# LabPower.net
KiCad netlist of a schematic drawn in EAGLE
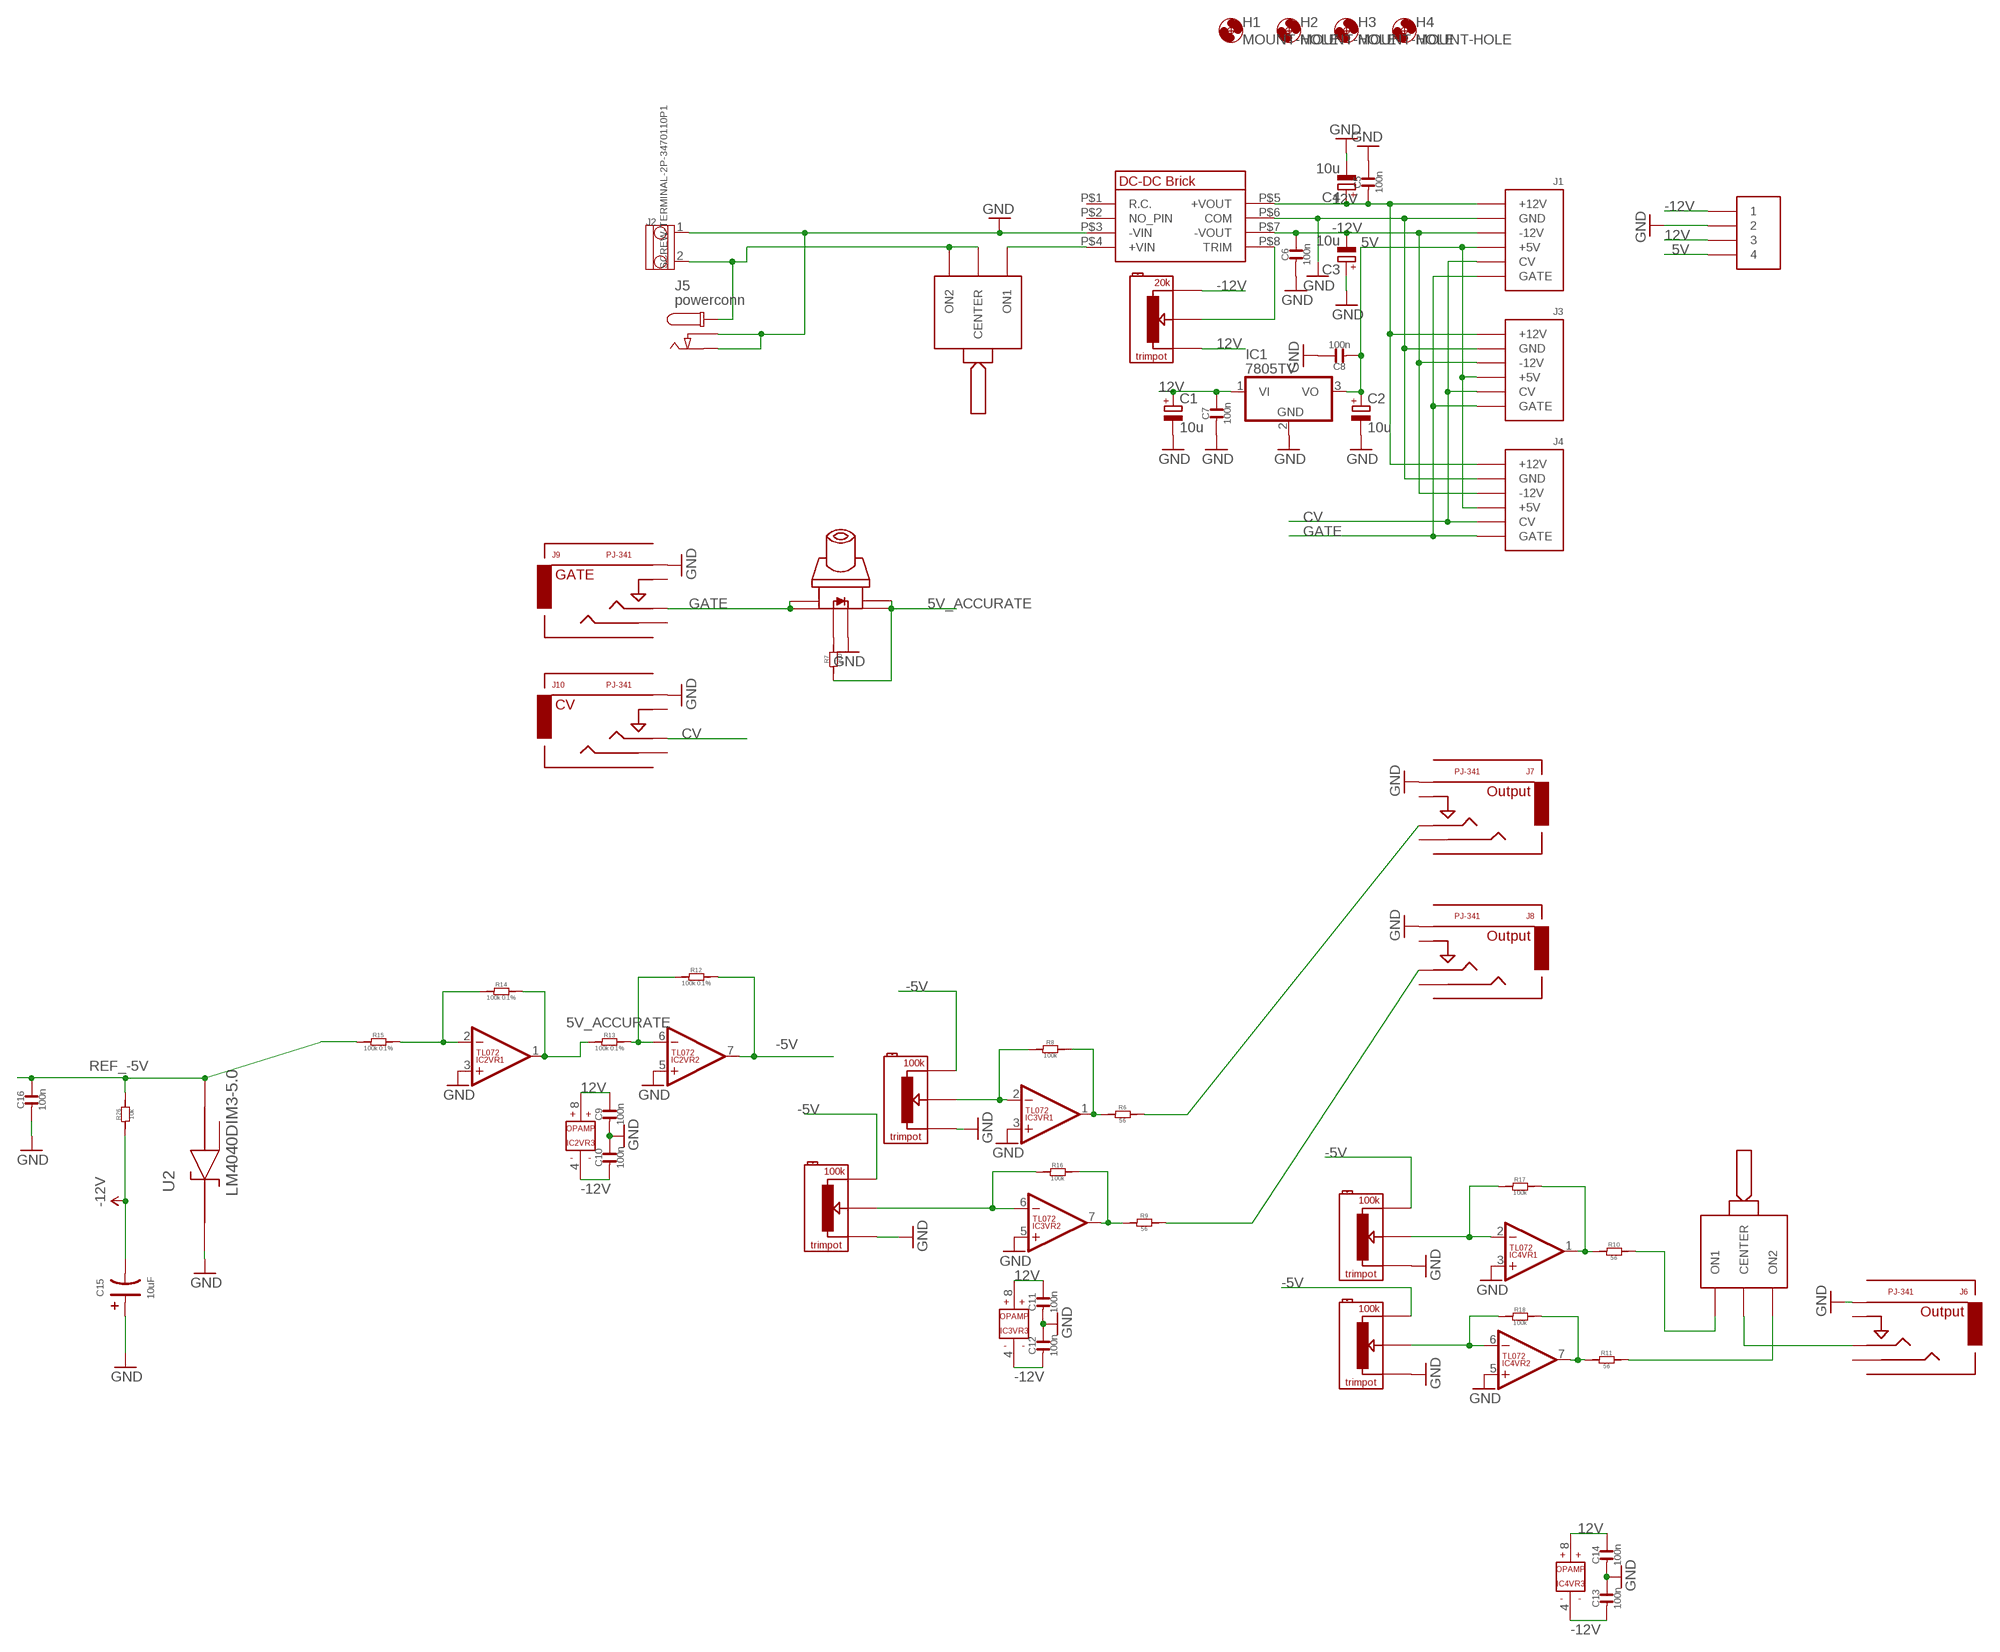
[diagram p0: schematic, sheet 1]

(export (version "E")
  (design (tool "Eeschema 10.0.6"))
  (components
    (comp (ref "C1")
      (value "10u")
      (footprint "eagle-import:CASE_B")
      (libsource (lib "eagle-import") (part "CAPACITOR_POL-CASE_B"))
    )
    (comp (ref "C2")
      (value "10u")
      (footprint "eagle-import:CASE_B")
      (libsource (lib "eagle-import") (part "CAPACITOR_POL-CASE_B"))
    )
    (comp (ref "C3")
      (value "10u")
      (footprint "eagle-import:CASE_B")
      (libsource (lib "eagle-import") (part "CAPACITOR_POL-CASE_B"))
    )
    (comp (ref "C4")
      (value "10u")
      (footprint "eagle-import:CASE_B")
      (libsource (lib "eagle-import") (part "CAPACITOR_POL-CASE_B"))
    )
    (comp (ref "C5")
      (value "100n")
      (footprint "eagle-import:C0603")
      (libsource (lib "eagle-import") (part "C-0603"))
    )
    (comp (ref "C6")
      (value "100n")
      (footprint "eagle-import:C0603")
      (libsource (lib "eagle-import") (part "C-0603"))
    )
    (comp (ref "C7")
      (value "100n")
      (footprint "eagle-import:C0603")
      (libsource (lib "eagle-import") (part "C-0603"))
    )
    (comp (ref "C8")
      (value "100n")
      (footprint "eagle-import:C0603")
      (libsource (lib "eagle-import") (part "C-0603"))
    )
    (comp (ref "C9")
      (value "100n")
      (footprint "eagle-import:C0603")
      (libsource (lib "eagle-import") (part "C-0603"))
    )
    (comp (ref "C10")
      (value "100n")
      (footprint "eagle-import:C0603")
      (libsource (lib "eagle-import") (part "C-0603"))
    )
    (comp (ref "C11")
      (value "100n")
      (footprint "eagle-import:C0603")
      (libsource (lib "eagle-import") (part "C-0603"))
    )
    (comp (ref "C12")
      (value "100n")
      (footprint "eagle-import:C0603")
      (libsource (lib "eagle-import") (part "C-0603"))
    )
    (comp (ref "C13")
      (value "100n")
      (footprint "eagle-import:C0603")
      (libsource (lib "eagle-import") (part "C-0603"))
    )
    (comp (ref "C14")
      (value "100n")
      (footprint "eagle-import:C0603")
      (libsource (lib "eagle-import") (part "C-0603"))
    )
    (comp (ref "C15")
      (value "10uF")
      (footprint "eagle-import:CASE-A_3216")
      (fields (field (name "MF") "AVX") (field (name "MPN") "TAJB106K020RNJ"))
      (libsource (lib "eagle-import") (part "C-POLAR-A"))
    )
    (comp (ref "C16")
      (value "100n")
      (footprint "eagle-import:C0603")
      (fields (field (name "MF") "AVX") (field (name "MPN") "06035C104KAT2A"))
      (libsource (lib "eagle-import") (part "C-0603"))
    )
    (comp (ref "H1")
      (value "MOUNT-HOLE")
      (footprint "eagle-import:3.2-NOMARKINGS-SMALLSAFEZONE")
      (libsource (lib "eagle-import") (part "MOUNT-HOLE"))
    )
    (comp (ref "H2")
      (value "MOUNT-HOLE")
      (footprint "eagle-import:3.2-NOMARKINGS-SMALLSAFEZONE")
      (libsource (lib "eagle-import") (part "MOUNT-HOLE"))
    )
    (comp (ref "H3")
      (value "MOUNT-HOLE")
      (footprint "eagle-import:3.2-NOMARKINGS-SMALLSAFEZONE")
      (libsource (lib "eagle-import") (part "MOUNT-HOLE"))
    )
    (comp (ref "H4")
      (value "MOUNT-HOLE")
      (footprint "eagle-import:3.2-NOMARKINGS-SMALLSAFEZONE")
      (libsource (lib "eagle-import") (part "MOUNT-HOLE"))
    )
    (comp (ref "IC1")
      (value "7805TV")
      (footprint "eagle-import:TO220V")
      (libsource (lib "eagle-import") (part "78TV05"))
    )
    (comp (ref "IC2")
      (value "TL072")
      (footprint "eagle-import:SO08")
      (libsource (lib "eagle-import") (part "TL072"))
    )
    (comp (ref "IC3")
      (value "TL072")
      (footprint "eagle-import:SO08")
      (libsource (lib "eagle-import") (part "TL072"))
    )
    (comp (ref "IC4")
      (value "TL072")
      (footprint "eagle-import:SO08")
      (libsource (lib "eagle-import") (part "TL072"))
    )
    (comp (ref "J1")
      (value "POWERSHROUDED")
      (footprint "eagle-import:POWER_16_SHROUDED")
      (libsource (lib "eagle-import") (part "POWERSHROUDED"))
    )
    (comp (ref "J2")
      (value "SCREW-TERMINAL-2P-3470110P1")
      (footprint "eagle-import:2P-5.0")
      (libsource (lib "eagle-import") (part "SCREW-TERMINAL-2P-3470110P1"))
    )
    (comp (ref "J3")
      (value "POWER_SHROUDED_NOTEXT")
      (footprint "eagle-import:POWER_16_SHROUDED_NOTEXT")
      (libsource (lib "eagle-import") (part "POWER_SHROUDED_NOTEXT"))
    )
    (comp (ref "J4")
      (value "POWER_SHROUDED_NOTEXT")
      (footprint "eagle-import:POWER_16_SHROUDED_NOTEXT")
      (libsource (lib "eagle-import") (part "POWER_SHROUDED_NOTEXT"))
    )
    (comp (ref "J5")
      (value "powerconn")
      (footprint "eagle-import:DC_BARREL_JACK_PTH_2MM_2")
      (libsource (lib "eagle-import") (part "CON_DC_M-DC_PTH2"))
    )
    (comp (ref "J6")
      (value "PJ-341")
      (footprint "eagle-import:3.5MM-JACK-SWITCH-13MM-OUTPUT")
      (libsource (lib "eagle-import") (part "AUDIO-JACKOUTPUT"))
    )
    (comp (ref "J7")
      (value "PJ-341")
      (footprint "eagle-import:3.5MM-JACK-SWITCH-13MM-OUTPUT")
      (libsource (lib "eagle-import") (part "AUDIO-JACKOUTPUT"))
    )
    (comp (ref "J8")
      (value "PJ-341")
      (footprint "eagle-import:3.5MM-JACK-SWITCH-13MM-OUTPUT")
      (libsource (lib "eagle-import") (part "AUDIO-JACKOUTPUT"))
    )
    (comp (ref "J9")
      (value "PJ-341")
      (footprint "eagle-import:3.5MM-JACK-SWITCH-13MM-INPUT")
      (fields (field (name "DESC") "GATE"))
      (libsource (lib "eagle-import") (part "AUDIO-JACKINPUT"))
    )
    (comp (ref "J10")
      (value "PJ-341")
      (footprint "eagle-import:3.5MM-JACK-SWITCH-13MM-INPUT")
      (fields (field (name "DESC") "CV"))
      (libsource (lib "eagle-import") (part "AUDIO-JACKINPUT"))
    )
    (comp (ref "R1")
      (value "20k")
      (footprint "eagle-import:TRIMPOT")
      (libsource (lib "eagle-import") (part "TRIMPOT"))
    )
    (comp (ref "R2")
      (value "100k")
      (footprint "eagle-import:TRIMPOT")
      (libsource (lib "eagle-import") (part "TRIMPOT"))
    )
    (comp (ref "R3")
      (value "100k")
      (footprint "eagle-import:TRIMPOT")
      (libsource (lib "eagle-import") (part "TRIMPOT"))
    )
    (comp (ref "R4")
      (value "100k")
      (footprint "eagle-import:TRIMPOT")
      (libsource (lib "eagle-import") (part "TRIMPOT"))
    )
    (comp (ref "R5")
      (value "100k")
      (footprint "eagle-import:TRIMPOT")
      (libsource (lib "eagle-import") (part "TRIMPOT"))
    )
    (comp (ref "R6")
      (value "56")
      (footprint "eagle-import:R0603")
      (libsource (lib "eagle-import") (part "R-0603"))
    )
    (comp (ref "R7")
      (value "200")
      (footprint "eagle-import:R0603")
      (libsource (lib "eagle-import") (part "R-0603"))
    )
    (comp (ref "R8")
      (value "100k")
      (footprint "eagle-import:R0603")
      (libsource (lib "eagle-import") (part "R-0603"))
    )
    (comp (ref "R9")
      (value "56")
      (footprint "eagle-import:R0603")
      (libsource (lib "eagle-import") (part "R-0603"))
    )
    (comp (ref "R10")
      (value "56")
      (footprint "eagle-import:R0603")
      (libsource (lib "eagle-import") (part "R-0603"))
    )
    (comp (ref "R11")
      (value "56")
      (footprint "eagle-import:R0603")
      (libsource (lib "eagle-import") (part "R-0603"))
    )
    (comp (ref "R12")
      (value "100k 0.1%")
      (footprint "eagle-import:R0603")
      (libsource (lib "eagle-import") (part "R-0603"))
    )
    (comp (ref "R13")
      (value "100k 0.1%")
      (footprint "eagle-import:R0603")
      (libsource (lib "eagle-import") (part "R-0603"))
    )
    (comp (ref "R14")
      (value "100k 0.1%")
      (footprint "eagle-import:R0603")
      (libsource (lib "eagle-import") (part "R-0603"))
    )
    (comp (ref "R15")
      (value "100k 0.1%")
      (footprint "eagle-import:R0603")
      (libsource (lib "eagle-import") (part "R-0603"))
    )
    (comp (ref "R16")
      (value "100k")
      (footprint "eagle-import:R0603")
      (libsource (lib "eagle-import") (part "R-0603"))
    )
    (comp (ref "R17")
      (value "100k")
      (footprint "eagle-import:R0603")
      (libsource (lib "eagle-import") (part "R-0603"))
    )
    (comp (ref "R18")
      (value "100k")
      (footprint "eagle-import:R0603")
      (libsource (lib "eagle-import") (part "R-0603"))
    )
    (comp (ref "R26")
      (value "10k")
      (footprint "eagle-import:R0603")
      (libsource (lib "eagle-import") (part "R-0603"))
    )
    (comp (ref "S1")
      (value "ONOFFON")
      (footprint "eagle-import:MULTICOMP1MS-ONOFFON")
      (libsource (lib "eagle-import") (part "ONOFFON"))
    )
    (comp (ref "S2")
      (value "ONOFFON")
      (footprint "eagle-import:MULTICOMP1MS-ONOFFON")
      (libsource (lib "eagle-import") (part "ONOFFON"))
    )
    (comp (ref "S3")
      (value "SWITCH_W_LED_PB6149L-X-102YELLOW")
      (footprint "eagle-import:PB6149L")
      (libsource (lib "eagle-import") (part "SWITCH_W_LED_PB6149L-X-102YELLOW"))
    )
    (comp (ref "U$1")
      (value "DKA30")
      (footprint "eagle-import:MEANWELL_DKA30")
      (libsource (lib "eagle-import") (part "DKA30"))
    )
    (comp (ref "U$2")
      (value "4PIN5MM")
      (footprint "eagle-import:4PIN5MM")
      (libsource (lib "eagle-import") (part "4PIN5MM"))
    )
    (comp (ref "U2")
      (value "LM4040DIM3-5.0")
      (footprint "eagle-import:SOT95P237X112-3N")
      (fields (field (name "MF") "TEXAS INSTRUMENTS") (field (name "OC_FARNELL") "9778330"))
      (libsource (lib "eagle-import") (part "LM4040DIM3-5.0"))
    )
  )
  (nets
    (net (code "1") (name "-12V") (class "Default")
      (node (ref "C10") (pin "1") (pinfunction "1_1") (pintype "bidirectional"))
      (node (ref "C12") (pin "1") (pinfunction "1_1") (pintype "bidirectional"))
      (node (ref "C13") (pin "1") (pinfunction "1_1") (pintype "bidirectional"))
      (node (ref "C15") (pin "-") (pinfunction "2_-") (pintype "bidirectional"))
      (node (ref "C3") (pin "-") (pinfunction "-_-") (pintype "passive"))
      (node (ref "C6") (pin "2") (pinfunction "2_2") (pintype "bidirectional"))
      (node (ref "IC2") (pin "4") (pinfunction "V-_4") (pintype "power_in"))
      (node (ref "IC3") (pin "4") (pinfunction "V-_4") (pintype "power_in"))
      (node (ref "IC4") (pin "4") (pinfunction "V-_4") (pintype "power_in"))
      (node (ref "J1") (pin "1") (pinfunction "-12V_1") (pintype "bidirectional"))
      (node (ref "J1") (pin "2") (pinfunction "-12V_2") (pintype "bidirectional"))
      (node (ref "J3") (pin "1") (pinfunction "-12V_1") (pintype "bidirectional"))
      (node (ref "J3") (pin "2") (pinfunction "-12V_2") (pintype "bidirectional"))
      (node (ref "J4") (pin "1") (pinfunction "-12V_1") (pintype "bidirectional"))
      (node (ref "J4") (pin "2") (pinfunction "-12V_2") (pintype "bidirectional"))
      (node (ref "R1") (pin "P$3") (pinfunction "P$3_P$3") (pintype "bidirectional"))
      (node (ref "R26") (pin "1") (pinfunction "1_1") (pintype "bidirectional"))
      (node (ref "U$1") (pin "P$7") (pinfunction "-VOUT_P$7") (pintype "bidirectional"))
      (node (ref "U$2") (pin "1") (pinfunction "1_1") (pintype "bidirectional"))
    )
    (net (code "2") (name "/-5V") (class "Default")
      (node (ref "IC2") (pin "7") (pinfunction "OUT_7") (pintype "output"))
      (node (ref "R12") (pin "2") (pinfunction "2_2") (pintype "bidirectional"))
      (node (ref "R2") (pin "P$3") (pinfunction "P$3_P$3") (pintype "bidirectional"))
      (node (ref "R3") (pin "P$3") (pinfunction "P$3_P$3") (pintype "bidirectional"))
      (node (ref "R4") (pin "P$3") (pinfunction "P$3_P$3") (pintype "bidirectional"))
      (node (ref "R5") (pin "P$3") (pinfunction "P$3_P$3") (pintype "bidirectional"))
    )
    (net (code "3") (name "/5V") (class "Default")
      (node (ref "C2") (pin "+") (pinfunction "+_+") (pintype "passive"))
      (node (ref "C8") (pin "1") (pinfunction "1_1") (pintype "bidirectional"))
      (node (ref "IC1") (pin "3") (pinfunction "VO_3") (pintype "passive"))
      (node (ref "J1") (pin "11") (pinfunction "+5V_11") (pintype "bidirectional"))
      (node (ref "J1") (pin "12") (pinfunction "+5V_12") (pintype "bidirectional"))
      (node (ref "J3") (pin "11") (pinfunction "+5V_11") (pintype "bidirectional"))
      (node (ref "J3") (pin "12") (pinfunction "+5V_12") (pintype "bidirectional"))
      (node (ref "J4") (pin "11") (pinfunction "+5V_11") (pintype "bidirectional"))
      (node (ref "J4") (pin "12") (pinfunction "+5V_12") (pintype "bidirectional"))
      (node (ref "U$2") (pin "4") (pinfunction "4_4") (pintype "bidirectional"))
    )
    (net (code "4") (name "/5V_ACCURATE") (class "Default")
      (node (ref "IC2") (pin "1") (pinfunction "OUT_1") (pintype "output"))
      (node (ref "R13") (pin "1") (pinfunction "1_1") (pintype "bidirectional"))
      (node (ref "R14") (pin "2") (pinfunction "2_2") (pintype "bidirectional"))
      (node (ref "R7") (pin "1") (pinfunction "1_1") (pintype "bidirectional"))
      (node (ref "S3") (pin "3") (pinfunction "3_3") (pintype "bidirectional"))
      (node (ref "S3") (pin "4") (pinfunction "4_4") (pintype "bidirectional"))
    )
    (net (code "5") (name "/12V") (class "Default")
      (node (ref "C1") (pin "+") (pinfunction "+_+") (pintype "passive"))
      (node (ref "C11") (pin "2") (pinfunction "2_2") (pintype "bidirectional"))
      (node (ref "C14") (pin "2") (pinfunction "2_2") (pintype "bidirectional"))
      (node (ref "C4") (pin "+") (pinfunction "+_+") (pintype "passive"))
      (node (ref "C5") (pin "1") (pinfunction "1_1") (pintype "bidirectional"))
      (node (ref "C7") (pin "2") (pinfunction "2_2") (pintype "bidirectional"))
      (node (ref "C9") (pin "2") (pinfunction "2_2") (pintype "bidirectional"))
      (node (ref "IC1") (pin "1") (pinfunction "VI_1") (pintype "input"))
      (node (ref "IC2") (pin "8") (pinfunction "V+_8") (pintype "power_in"))
      (node (ref "IC3") (pin "8") (pinfunction "V+_8") (pintype "power_in"))
      (node (ref "IC4") (pin "8") (pinfunction "V+_8") (pintype "power_in"))
      (node (ref "J1") (pin "10") (pinfunction "+12V_10") (pintype "bidirectional"))
      (node (ref "J1") (pin "9") (pinfunction "+12V_9") (pintype "bidirectional"))
      (node (ref "J3") (pin "10") (pinfunction "+12V_10") (pintype "bidirectional"))
      (node (ref "J3") (pin "9") (pinfunction "+12V_9") (pintype "bidirectional"))
      (node (ref "J4") (pin "10") (pinfunction "+12V_10") (pintype "bidirectional"))
      (node (ref "J4") (pin "9") (pinfunction "+12V_9") (pintype "bidirectional"))
      (node (ref "R1") (pin "P$1") (pinfunction "P$1_P$1") (pintype "bidirectional"))
      (node (ref "U$1") (pin "P$5") (pinfunction "+VOUT_P$5") (pintype "bidirectional"))
      (node (ref "U$2") (pin "3") (pinfunction "3_3") (pintype "bidirectional"))
    )
    (net (code "6") (name "/CV") (class "Default")
      (node (ref "J1") (pin "13") (pinfunction "CV_13") (pintype "bidirectional"))
      (node (ref "J1") (pin "14") (pinfunction "CV_14") (pintype "bidirectional"))
      (node (ref "J10") (pin "TIP@3") (pinfunction "TIP_TIP@3") (pintype "bidirectional"))
      (node (ref "J3") (pin "13") (pinfunction "CV_13") (pintype "bidirectional"))
      (node (ref "J3") (pin "14") (pinfunction "CV_14") (pintype "bidirectional"))
      (node (ref "J4") (pin "13") (pinfunction "CV_13") (pintype "bidirectional"))
      (node (ref "J4") (pin "14") (pinfunction "CV_14") (pintype "bidirectional"))
    )
    (net (code "7") (name "/GATE") (class "Default")
      (node (ref "J1") (pin "15") (pinfunction "GATE_15") (pintype "bidirectional"))
      (node (ref "J1") (pin "16") (pinfunction "GATE_16") (pintype "bidirectional"))
      (node (ref "J3") (pin "15") (pinfunction "GATE_15") (pintype "bidirectional"))
      (node (ref "J3") (pin "16") (pinfunction "GATE_16") (pintype "bidirectional"))
      (node (ref "J4") (pin "15") (pinfunction "GATE_15") (pintype "bidirectional"))
      (node (ref "J4") (pin "16") (pinfunction "GATE_16") (pintype "bidirectional"))
      (node (ref "J9") (pin "TIP@3") (pinfunction "TIP_TIP@3") (pintype "bidirectional"))
      (node (ref "S3") (pin "1") (pinfunction "1_1") (pintype "bidirectional"))
      (node (ref "S3") (pin "2") (pinfunction "2_2") (pintype "bidirectional"))
    )
    (net (code "8") (name "/REF_-5V") (class "Default")
      (node (ref "C16") (pin "2") (pinfunction "2_2") (pintype "bidirectional"))
      (node (ref "R15") (pin "1") (pinfunction "1_1") (pintype "bidirectional"))
      (node (ref "R26") (pin "2") (pinfunction "2_2") (pintype "bidirectional"))
      (node (ref "U2") (pin "2") (pinfunction "ANODE_2") (pintype "passive"))
    )
    (net (code "9") (name "GND") (class "Default")
      (node (ref "C1") (pin "-") (pinfunction "-_-") (pintype "passive"))
      (node (ref "C10") (pin "2") (pinfunction "2_2") (pintype "bidirectional"))
      (node (ref "C11") (pin "1") (pinfunction "1_1") (pintype "bidirectional"))
      (node (ref "C12") (pin "2") (pinfunction "2_2") (pintype "bidirectional"))
      (node (ref "C13") (pin "2") (pinfunction "2_2") (pintype "bidirectional"))
      (node (ref "C14") (pin "1") (pinfunction "1_1") (pintype "bidirectional"))
      (node (ref "C15") (pin "+") (pinfunction "1_+") (pintype "bidirectional"))
      (node (ref "C16") (pin "1") (pinfunction "1_1") (pintype "bidirectional"))
      (node (ref "C2") (pin "-") (pinfunction "-_-") (pintype "passive"))
      (node (ref "C3") (pin "+") (pinfunction "+_+") (pintype "passive"))
      (node (ref "C4") (pin "-") (pinfunction "-_-") (pintype "passive"))
      (node (ref "C5") (pin "2") (pinfunction "2_2") (pintype "bidirectional"))
      (node (ref "C6") (pin "1") (pinfunction "1_1") (pintype "bidirectional"))
      (node (ref "C7") (pin "1") (pinfunction "1_1") (pintype "bidirectional"))
      (node (ref "C8") (pin "2") (pinfunction "2_2") (pintype "bidirectional"))
      (node (ref "C9") (pin "1") (pinfunction "1_1") (pintype "bidirectional"))
      (node (ref "IC1") (pin "2") (pinfunction "GND_2") (pintype "passive"))
      (node (ref "IC2") (pin "3") (pinfunction "+IN_3") (pintype "input"))
      (node (ref "IC2") (pin "5") (pinfunction "+IN_5") (pintype "input"))
      (node (ref "IC3") (pin "3") (pinfunction "+IN_3") (pintype "input"))
      (node (ref "IC3") (pin "5") (pinfunction "+IN_5") (pintype "input"))
      (node (ref "IC4") (pin "3") (pinfunction "+IN_3") (pintype "input"))
      (node (ref "IC4") (pin "5") (pinfunction "+IN_5") (pintype "input"))
      (node (ref "J1") (pin "3") (pinfunction "GND_3") (pintype "bidirectional"))
      (node (ref "J1") (pin "4") (pinfunction "GND_4") (pintype "bidirectional"))
      (node (ref "J1") (pin "5") (pinfunction "GND_5") (pintype "bidirectional"))
      (node (ref "J1") (pin "6") (pinfunction "GND_6") (pintype "bidirectional"))
      (node (ref "J1") (pin "7") (pinfunction "GND_7") (pintype "bidirectional"))
      (node (ref "J1") (pin "8") (pinfunction "GND_8") (pintype "bidirectional"))
      (node (ref "J10") (pin "RING@3") (pinfunction "RING_RING@3") (pintype "bidirectional"))
      (node (ref "J2") (pin "1") (pinfunction "1_1") (pintype "bidirectional"))
      (node (ref "J3") (pin "3") (pinfunction "GND_3") (pintype "bidirectional"))
      (node (ref "J3") (pin "4") (pinfunction "GND_4") (pintype "bidirectional"))
      (node (ref "J3") (pin "5") (pinfunction "GND_5") (pintype "bidirectional"))
      (node (ref "J3") (pin "6") (pinfunction "GND_6") (pintype "bidirectional"))
      (node (ref "J3") (pin "7") (pinfunction "GND_7") (pintype "bidirectional"))
      (node (ref "J3") (pin "8") (pinfunction "GND_8") (pintype "bidirectional"))
      (node (ref "J4") (pin "3") (pinfunction "GND_3") (pintype "bidirectional"))
      (node (ref "J4") (pin "4") (pinfunction "GND_4") (pintype "bidirectional"))
      (node (ref "J4") (pin "5") (pinfunction "GND_5") (pintype "bidirectional"))
      (node (ref "J4") (pin "6") (pinfunction "GND_6") (pintype "bidirectional"))
      (node (ref "J4") (pin "7") (pinfunction "GND_7") (pintype "bidirectional"))
      (node (ref "J4") (pin "8") (pinfunction "GND_8") (pintype "bidirectional"))
      (node (ref "J5") (pin "P2") (pinfunction "P3_P2") (pintype "passive"))
      (node (ref "J5") (pin "P3") (pinfunction "P2_P3") (pintype "passive"))
      (node (ref "J6") (pin "RING@3") (pinfunction "RING_RING@3") (pintype "bidirectional"))
      (node (ref "J7") (pin "RING@3") (pinfunction "RING_RING@3") (pintype "bidirectional"))
      (node (ref "J8") (pin "RING@3") (pinfunction "RING_RING@3") (pintype "bidirectional"))
      (node (ref "J9") (pin "RING@3") (pinfunction "RING_RING@3") (pintype "bidirectional"))
      (node (ref "R2") (pin "P$1") (pinfunction "P$1_P$1") (pintype "bidirectional"))
      (node (ref "R3") (pin "P$1") (pinfunction "P$1_P$1") (pintype "bidirectional"))
      (node (ref "R4") (pin "P$1") (pinfunction "P$1_P$1") (pintype "bidirectional"))
      (node (ref "R5") (pin "P$1") (pinfunction "P$1_P$1") (pintype "bidirectional"))
      (node (ref "S3") (pin "LEDNEG") (pinfunction "NEG_LEDNEG") (pintype "bidirectional"))
      (node (ref "U$1") (pin "P$3") (pinfunction "-VIN_P$3") (pintype "bidirectional"))
      (node (ref "U$1") (pin "P$6") (pinfunction "COM_P$6") (pintype "bidirectional"))
      (node (ref "U$2") (pin "2") (pinfunction "2_2") (pintype "bidirectional"))
      (node (ref "U2") (pin "1") (pinfunction "CATHODE_1") (pintype "passive"))
    )
    (net (code "10") (name "Net-(IC2A--IN)") (class "Default")
      (node (ref "IC2") (pin "2") (pinfunction "-IN_2") (pintype "input"))
      (node (ref "R14") (pin "1") (pinfunction "1_1") (pintype "bidirectional"))
      (node (ref "R15") (pin "2") (pinfunction "2_2") (pintype "bidirectional"))
    )
    (net (code "11") (name "Net-(IC2B--IN)") (class "Default")
      (node (ref "IC2") (pin "6") (pinfunction "-IN_6") (pintype "input"))
      (node (ref "R12") (pin "1") (pinfunction "1_1") (pintype "bidirectional"))
      (node (ref "R13") (pin "2") (pinfunction "2_2") (pintype "bidirectional"))
    )
    (net (code "12") (name "Net-(IC3A--IN)") (class "Default")
      (node (ref "IC3") (pin "2") (pinfunction "-IN_2") (pintype "input"))
      (node (ref "R3") (pin "P$2") (pinfunction "P$2_P$2") (pintype "bidirectional"))
      (node (ref "R8") (pin "1") (pinfunction "1_1") (pintype "bidirectional"))
    )
    (net (code "13") (name "Net-(IC3A-OUT)") (class "Default")
      (node (ref "IC3") (pin "1") (pinfunction "OUT_1") (pintype "output"))
      (node (ref "R6") (pin "1") (pinfunction "1_1") (pintype "bidirectional"))
      (node (ref "R8") (pin "2") (pinfunction "2_2") (pintype "bidirectional"))
    )
    (net (code "14") (name "Net-(IC3B--IN)") (class "Default")
      (node (ref "IC3") (pin "6") (pinfunction "-IN_6") (pintype "input"))
      (node (ref "R16") (pin "1") (pinfunction "1_1") (pintype "bidirectional"))
      (node (ref "R4") (pin "P$2") (pinfunction "P$2_P$2") (pintype "bidirectional"))
    )
    (net (code "15") (name "Net-(IC3B-OUT)") (class "Default")
      (node (ref "IC3") (pin "7") (pinfunction "OUT_7") (pintype "output"))
      (node (ref "R16") (pin "2") (pinfunction "2_2") (pintype "bidirectional"))
      (node (ref "R9") (pin "1") (pinfunction "1_1") (pintype "bidirectional"))
    )
    (net (code "16") (name "Net-(IC4A--IN)") (class "Default")
      (node (ref "IC4") (pin "2") (pinfunction "-IN_2") (pintype "input"))
      (node (ref "R17") (pin "1") (pinfunction "1_1") (pintype "bidirectional"))
      (node (ref "R5") (pin "P$2") (pinfunction "P$2_P$2") (pintype "bidirectional"))
    )
    (net (code "17") (name "Net-(IC4A-OUT)") (class "Default")
      (node (ref "IC4") (pin "1") (pinfunction "OUT_1") (pintype "output"))
      (node (ref "R10") (pin "1") (pinfunction "1_1") (pintype "bidirectional"))
      (node (ref "R17") (pin "2") (pinfunction "2_2") (pintype "bidirectional"))
    )
    (net (code "18") (name "Net-(IC4B--IN)") (class "Default")
      (node (ref "IC4") (pin "6") (pinfunction "-IN_6") (pintype "input"))
      (node (ref "R18") (pin "1") (pinfunction "1_1") (pintype "bidirectional"))
      (node (ref "R2") (pin "P$2") (pinfunction "P$2_P$2") (pintype "bidirectional"))
    )
    (net (code "19") (name "Net-(IC4B-OUT)") (class "Default")
      (node (ref "IC4") (pin "7") (pinfunction "OUT_7") (pintype "output"))
      (node (ref "R11") (pin "1") (pinfunction "1_1") (pintype "bidirectional"))
      (node (ref "R18") (pin "2") (pinfunction "2_2") (pintype "bidirectional"))
    )
    (net (code "20") (name "Net-(J6-TIP)") (class "Default")
      (node (ref "J6") (pin "TIP@3") (pinfunction "TIP_TIP@3") (pintype "bidirectional"))
      (node (ref "S2") (pin "2") (pinfunction "CENTER_2") (pintype "bidirectional"))
    )
    (net (code "21") (name "Net-(J7-TIP)") (class "Default")
      (node (ref "J7") (pin "TIP@3") (pinfunction "TIP_TIP@3") (pintype "bidirectional"))
      (node (ref "R6") (pin "2") (pinfunction "2_2") (pintype "bidirectional"))
    )
    (net (code "22") (name "Net-(J8-TIP)") (class "Default")
      (node (ref "J8") (pin "TIP@3") (pinfunction "TIP_TIP@3") (pintype "bidirectional"))
      (node (ref "R9") (pin "2") (pinfunction "2_2") (pintype "bidirectional"))
    )
    (net (code "23") (name "Net-(S1-CENTER)") (class "Default")
      (node (ref "J2") (pin "2") (pinfunction "2_2") (pintype "bidirectional"))
      (node (ref "J5") (pin "P1") (pinfunction "P1_P1") (pintype "passive"))
      (node (ref "S1") (pin "2") (pinfunction "CENTER_2") (pintype "bidirectional"))
      (node (ref "S1") (pin "3") (pinfunction "ON2_3") (pintype "bidirectional"))
    )
    (net (code "24") (name "Net-(S1-ON1)") (class "Default")
      (node (ref "S1") (pin "1") (pinfunction "ON1_1") (pintype "bidirectional"))
      (node (ref "U$1") (pin "P$4") (pinfunction "+VIN_P$4") (pintype "bidirectional"))
    )
    (net (code "25") (name "Net-(S2-ON1)") (class "Default")
      (node (ref "R10") (pin "2") (pinfunction "2_2") (pintype "bidirectional"))
      (node (ref "S2") (pin "1") (pinfunction "ON1_1") (pintype "bidirectional"))
    )
    (net (code "26") (name "Net-(S2-ON2)") (class "Default")
      (node (ref "R11") (pin "2") (pinfunction "2_2") (pintype "bidirectional"))
      (node (ref "S2") (pin "3") (pinfunction "ON2_3") (pintype "bidirectional"))
    )
    (net (code "27") (name "Net-(S3-POS)") (class "Default")
      (node (ref "R7") (pin "2") (pinfunction "2_2") (pintype "bidirectional"))
      (node (ref "S3") (pin "LEDPOS") (pinfunction "POS_LEDPOS") (pintype "bidirectional"))
    )
    (net (code "28") (name "Net-(U$1-TRIM)") (class "Default")
      (node (ref "R1") (pin "P$2") (pinfunction "P$2_P$2") (pintype "bidirectional"))
      (node (ref "U$1") (pin "P$8") (pinfunction "TRIM_P$8") (pintype "bidirectional"))
    )
    (net (code "29") (name "unconnected-(J6-SECOND-PadSECOND@3)") (class "Default")
      (node (ref "J6") (pin "SECOND@3") (pinfunction "SECOND_SECOND@3") (pintype "bidirectional"))
    )
    (net (code "30") (name "unconnected-(J6-SWITCH-PadSWITCH@3)") (class "Default")
      (node (ref "J6") (pin "SWITCH@3") (pinfunction "SWITCH_SWITCH@3") (pintype "bidirectional"))
    )
    (net (code "31") (name "unconnected-(J7-SECOND-PadSECOND@3)") (class "Default")
      (node (ref "J7") (pin "SECOND@3") (pinfunction "SECOND_SECOND@3") (pintype "bidirectional"))
    )
    (net (code "32") (name "unconnected-(J7-SWITCH-PadSWITCH@3)") (class "Default")
      (node (ref "J7") (pin "SWITCH@3") (pinfunction "SWITCH_SWITCH@3") (pintype "bidirectional"))
    )
    (net (code "33") (name "unconnected-(J8-SECOND-PadSECOND@3)") (class "Default")
      (node (ref "J8") (pin "SECOND@3") (pinfunction "SECOND_SECOND@3") (pintype "bidirectional"))
    )
    (net (code "34") (name "unconnected-(J8-SWITCH-PadSWITCH@3)") (class "Default")
      (node (ref "J8") (pin "SWITCH@3") (pinfunction "SWITCH_SWITCH@3") (pintype "bidirectional"))
    )
    (net (code "35") (name "unconnected-(J9-SECOND-PadSECOND@3)") (class "Default")
      (node (ref "J9") (pin "SECOND@3") (pinfunction "SECOND_SECOND@3") (pintype "bidirectional"))
    )
    (net (code "36") (name "unconnected-(J9-SWITCH-PadSWITCH@3)") (class "Default")
      (node (ref "J9") (pin "SWITCH@3") (pinfunction "SWITCH_SWITCH@3") (pintype "bidirectional"))
    )
    (net (code "37") (name "unconnected-(J10-SECOND-PadSECOND@3)") (class "Default")
      (node (ref "J10") (pin "SECOND@3") (pinfunction "SECOND_SECOND@3") (pintype "bidirectional"))
    )
    (net (code "38") (name "unconnected-(J10-SWITCH-PadSWITCH@3)") (class "Default")
      (node (ref "J10") (pin "SWITCH@3") (pinfunction "SWITCH_SWITCH@3") (pintype "bidirectional"))
    )
    (net (code "39") (name "unconnected-(U$1-NO_PIN-PadP$2)") (class "Default")
      (node (ref "U$1") (pin "P$2") (pinfunction "NO_PIN_P$2") (pintype "bidirectional"))
    )
    (net (code "40") (name "unconnected-(U$1-R.C.-PadP$1)") (class "Default")
      (node (ref "U$1") (pin "P$1") (pinfunction "R.C._P$1") (pintype "bidirectional"))
    )
    (net (code "41") (name "unconnected-(U2-NC-Pad3)") (class "Default")
      (node (ref "U2") (pin "3") (pinfunction "NC_3") (pintype "passive"))
    )
  )
)
